# Input2.net
KiCad netlist of a schematic drawn in Altium Designer
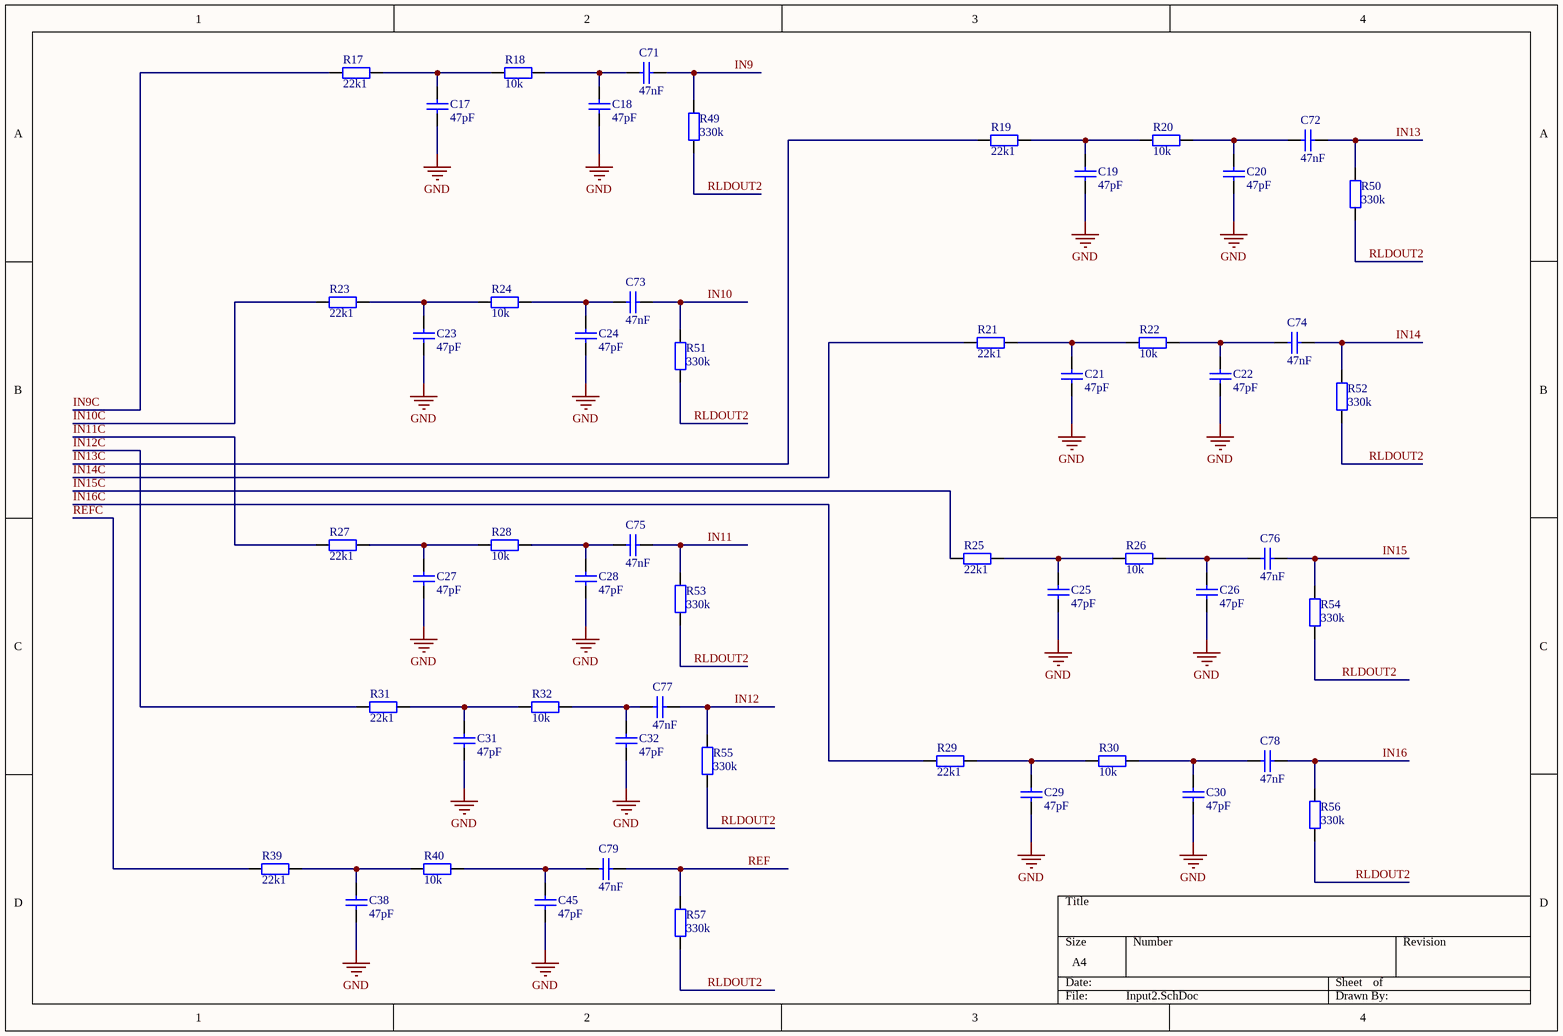
[diagram p0: Input2.SchDoc]

(export (version "E")
  (design (tool "Eeschema 10.0.6"))
  (components
    (comp (ref "C17")
      (value "47pF")
      (footprint "C0603")
      (description "Capacitor")
      (fields (field (name "PUBLISHER") "Altium Limited"))
      (libsource (lib "Miscellaneous Devices") (part "Cap"))
    )
    (comp (ref "C18")
      (value "47pF")
      (footprint "C0603")
      (description "Capacitor")
      (fields (field (name "PUBLISHER") "Altium Limited"))
      (libsource (lib "Miscellaneous Devices") (part "Cap"))
    )
    (comp (ref "C19")
      (value "47pF")
      (footprint "C0603")
      (description "Capacitor")
      (fields (field (name "PUBLISHER") "Altium Limited"))
      (libsource (lib "Miscellaneous Devices") (part "Cap"))
    )
    (comp (ref "C20")
      (value "47pF")
      (footprint "C0603")
      (description "Capacitor")
      (fields (field (name "PUBLISHER") "Altium Limited"))
      (libsource (lib "Miscellaneous Devices") (part "Cap"))
    )
    (comp (ref "C21")
      (value "47pF")
      (footprint "C0603")
      (description "Capacitor")
      (fields (field (name "PUBLISHER") "Altium Limited"))
      (libsource (lib "Miscellaneous Devices") (part "Cap"))
    )
    (comp (ref "C22")
      (value "47pF")
      (footprint "C0603")
      (description "Capacitor")
      (fields (field (name "PUBLISHER") "Altium Limited"))
      (libsource (lib "Miscellaneous Devices") (part "Cap"))
    )
    (comp (ref "C23")
      (value "47pF")
      (footprint "C0603")
      (description "Capacitor")
      (fields (field (name "PUBLISHER") "Altium Limited"))
      (libsource (lib "Miscellaneous Devices") (part "Cap"))
    )
    (comp (ref "C24")
      (value "47pF")
      (footprint "C0603")
      (description "Capacitor")
      (fields (field (name "PUBLISHER") "Altium Limited"))
      (libsource (lib "Miscellaneous Devices") (part "Cap"))
    )
    (comp (ref "C25")
      (value "47pF")
      (footprint "C0603")
      (description "Capacitor")
      (fields (field (name "PUBLISHER") "Altium Limited"))
      (libsource (lib "Miscellaneous Devices") (part "Cap"))
    )
    (comp (ref "C26")
      (value "47pF")
      (footprint "C0603")
      (description "Capacitor")
      (fields (field (name "PUBLISHER") "Altium Limited"))
      (libsource (lib "Miscellaneous Devices") (part "Cap"))
    )
    (comp (ref "C27")
      (value "47pF")
      (footprint "C0603")
      (description "Capacitor")
      (fields (field (name "PUBLISHER") "Altium Limited"))
      (libsource (lib "Miscellaneous Devices") (part "Cap"))
    )
    (comp (ref "C28")
      (value "47pF")
      (footprint "C0603")
      (description "Capacitor")
      (fields (field (name "PUBLISHER") "Altium Limited"))
      (libsource (lib "Miscellaneous Devices") (part "Cap"))
    )
    (comp (ref "C29")
      (value "47pF")
      (footprint "C0603")
      (description "Capacitor")
      (fields (field (name "PUBLISHER") "Altium Limited"))
      (libsource (lib "Miscellaneous Devices") (part "Cap"))
    )
    (comp (ref "C30")
      (value "47pF")
      (footprint "C0603")
      (description "Capacitor")
      (fields (field (name "PUBLISHER") "Altium Limited"))
      (libsource (lib "Miscellaneous Devices") (part "Cap"))
    )
    (comp (ref "C31")
      (value "47pF")
      (footprint "C0603")
      (description "Capacitor")
      (fields (field (name "PUBLISHER") "Altium Limited"))
      (libsource (lib "Miscellaneous Devices") (part "Cap"))
    )
    (comp (ref "C32")
      (value "47pF")
      (footprint "C0603")
      (description "Capacitor")
      (fields (field (name "PUBLISHER") "Altium Limited"))
      (libsource (lib "Miscellaneous Devices") (part "Cap"))
    )
    (comp (ref "C38")
      (value "47pF")
      (footprint "C0603")
      (description "Capacitor")
      (fields (field (name "PUBLISHER") "Altium Limited"))
      (libsource (lib "Miscellaneous Devices") (part "Cap"))
    )
    (comp (ref "C45")
      (value "47pF")
      (footprint "C0603")
      (description "Capacitor")
      (fields (field (name "PUBLISHER") "Altium Limited"))
      (libsource (lib "Miscellaneous Devices") (part "Cap"))
    )
    (comp (ref "C71")
      (value "47nF")
      (footprint "C0603")
      (description "Capacitor")
      (fields (field (name "PUBLISHER") "Altium Limited"))
      (libsource (lib "Miscellaneous Devices") (part "Cap"))
    )
    (comp (ref "C72")
      (value "47nF")
      (footprint "C0603")
      (description "Capacitor")
      (fields (field (name "PUBLISHER") "Altium Limited"))
      (libsource (lib "Miscellaneous Devices") (part "Cap"))
    )
    (comp (ref "C73")
      (value "47nF")
      (footprint "C0603")
      (description "Capacitor")
      (fields (field (name "PUBLISHER") "Altium Limited"))
      (libsource (lib "Miscellaneous Devices") (part "Cap"))
    )
    (comp (ref "C74")
      (value "47nF")
      (footprint "C0603")
      (description "Capacitor")
      (fields (field (name "PUBLISHER") "Altium Limited"))
      (libsource (lib "Miscellaneous Devices") (part "Cap"))
    )
    (comp (ref "C75")
      (value "47nF")
      (footprint "C0603")
      (description "Capacitor")
      (fields (field (name "PUBLISHER") "Altium Limited"))
      (libsource (lib "Miscellaneous Devices") (part "Cap"))
    )
    (comp (ref "C76")
      (value "47nF")
      (footprint "C0603")
      (description "Capacitor")
      (fields (field (name "PUBLISHER") "Altium Limited"))
      (libsource (lib "Miscellaneous Devices") (part "Cap"))
    )
    (comp (ref "C77")
      (value "47nF")
      (footprint "C0603")
      (description "Capacitor")
      (fields (field (name "PUBLISHER") "Altium Limited"))
      (libsource (lib "Miscellaneous Devices") (part "Cap"))
    )
    (comp (ref "C78")
      (value "47nF")
      (footprint "C0603")
      (description "Capacitor")
      (fields (field (name "PUBLISHER") "Altium Limited"))
      (libsource (lib "Miscellaneous Devices") (part "Cap"))
    )
    (comp (ref "C79")
      (value "47nF")
      (footprint "C0603")
      (description "Capacitor")
      (fields (field (name "PUBLISHER") "Altium Limited"))
      (libsource (lib "Miscellaneous Devices") (part "Cap"))
    )
    (comp (ref "R17")
      (value "22k1")
      (footprint "RES0603")
      (description "Resistor")
      (fields (field (name "PUBLISHER") "Altium Limited"))
      (libsource (lib "Miscellaneous Devices") (part "Res2"))
    )
    (comp (ref "R18")
      (value "10k")
      (footprint "RES0603")
      (description "Resistor")
      (fields (field (name "PUBLISHER") "Altium Limited"))
      (libsource (lib "Miscellaneous Devices") (part "Res2"))
    )
    (comp (ref "R19")
      (value "22k1")
      (footprint "RES0603")
      (description "Resistor")
      (fields (field (name "PUBLISHER") "Altium Limited"))
      (libsource (lib "Miscellaneous Devices") (part "Res2"))
    )
    (comp (ref "R20")
      (value "10k")
      (footprint "RES0603")
      (description "Resistor")
      (fields (field (name "PUBLISHER") "Altium Limited"))
      (libsource (lib "Miscellaneous Devices") (part "Res2"))
    )
    (comp (ref "R21")
      (value "22k1")
      (footprint "RES0603")
      (description "Resistor")
      (fields (field (name "PUBLISHER") "Altium Limited"))
      (libsource (lib "Miscellaneous Devices") (part "Res2"))
    )
    (comp (ref "R22")
      (value "10k")
      (footprint "RES0603")
      (description "Resistor")
      (fields (field (name "PUBLISHER") "Altium Limited"))
      (libsource (lib "Miscellaneous Devices") (part "Res2"))
    )
    (comp (ref "R23")
      (value "22k1")
      (footprint "RES0603")
      (description "Resistor")
      (fields (field (name "PUBLISHER") "Altium Limited"))
      (libsource (lib "Miscellaneous Devices") (part "Res2"))
    )
    (comp (ref "R24")
      (value "10k")
      (footprint "RES0603")
      (description "Resistor")
      (fields (field (name "PUBLISHER") "Altium Limited"))
      (libsource (lib "Miscellaneous Devices") (part "Res2"))
    )
    (comp (ref "R25")
      (value "22k1")
      (footprint "RES0603")
      (description "Resistor")
      (fields (field (name "PUBLISHER") "Altium Limited"))
      (libsource (lib "Miscellaneous Devices") (part "Res2"))
    )
    (comp (ref "R26")
      (value "10k")
      (footprint "RES0603")
      (description "Resistor")
      (fields (field (name "PUBLISHER") "Altium Limited"))
      (libsource (lib "Miscellaneous Devices") (part "Res2"))
    )
    (comp (ref "R27")
      (value "22k1")
      (footprint "RES0603")
      (description "Resistor")
      (fields (field (name "PUBLISHER") "Altium Limited"))
      (libsource (lib "Miscellaneous Devices") (part "Res2"))
    )
    (comp (ref "R28")
      (value "10k")
      (footprint "RES0603")
      (description "Resistor")
      (fields (field (name "PUBLISHER") "Altium Limited"))
      (libsource (lib "Miscellaneous Devices") (part "Res2"))
    )
    (comp (ref "R29")
      (value "22k1")
      (footprint "RES0603")
      (description "Resistor")
      (fields (field (name "PUBLISHER") "Altium Limited"))
      (libsource (lib "Miscellaneous Devices") (part "Res2"))
    )
    (comp (ref "R30")
      (value "10k")
      (footprint "RES0603")
      (description "Resistor")
      (fields (field (name "PUBLISHER") "Altium Limited"))
      (libsource (lib "Miscellaneous Devices") (part "Res2"))
    )
    (comp (ref "R31")
      (value "22k1")
      (footprint "RES0603")
      (description "Resistor")
      (fields (field (name "PUBLISHER") "Altium Limited"))
      (libsource (lib "Miscellaneous Devices") (part "Res2"))
    )
    (comp (ref "R32")
      (value "10k")
      (footprint "RES0603")
      (description "Resistor")
      (fields (field (name "PUBLISHER") "Altium Limited"))
      (libsource (lib "Miscellaneous Devices") (part "Res2"))
    )
    (comp (ref "R39")
      (value "22k1")
      (footprint "RES0603")
      (description "Resistor")
      (fields (field (name "PUBLISHER") "Altium Limited"))
      (libsource (lib "Miscellaneous Devices") (part "Res2"))
    )
    (comp (ref "R40")
      (value "10k")
      (footprint "RES0603")
      (description "Resistor")
      (fields (field (name "PUBLISHER") "Altium Limited"))
      (libsource (lib "Miscellaneous Devices") (part "Res2"))
    )
    (comp (ref "R49")
      (value "330k")
      (footprint "RES0603")
      (description "Resistor")
      (fields (field (name "PUBLISHER") "Altium Limited"))
      (libsource (lib "") (part "Res2_1"))
    )
    (comp (ref "R50")
      (value "330k")
      (footprint "RES0603")
      (description "Resistor")
      (fields (field (name "PUBLISHER") "Altium Limited"))
      (libsource (lib "") (part "Res2_1"))
    )
    (comp (ref "R51")
      (value "330k")
      (footprint "RES0603")
      (description "Resistor")
      (fields (field (name "PUBLISHER") "Altium Limited"))
      (libsource (lib "") (part "Res2_1"))
    )
    (comp (ref "R52")
      (value "330k")
      (footprint "RES0603")
      (description "Resistor")
      (fields (field (name "PUBLISHER") "Altium Limited"))
      (libsource (lib "") (part "Res2_1"))
    )
    (comp (ref "R53")
      (value "330k")
      (footprint "RES0603")
      (description "Resistor")
      (fields (field (name "PUBLISHER") "Altium Limited"))
      (libsource (lib "") (part "Res2_1"))
    )
    (comp (ref "R54")
      (value "330k")
      (footprint "RES0603")
      (description "Resistor")
      (fields (field (name "PUBLISHER") "Altium Limited"))
      (libsource (lib "") (part "Res2_1"))
    )
    (comp (ref "R55")
      (value "330k")
      (footprint "RES0603")
      (description "Resistor")
      (fields (field (name "PUBLISHER") "Altium Limited"))
      (libsource (lib "") (part "Res2_1"))
    )
    (comp (ref "R56")
      (value "330k")
      (footprint "RES0603")
      (description "Resistor")
      (fields (field (name "PUBLISHER") "Altium Limited"))
      (libsource (lib "") (part "Res2_1"))
    )
    (comp (ref "R57")
      (value "330k")
      (footprint "RES0603")
      (description "Resistor")
      (fields (field (name "PUBLISHER") "Altium Limited"))
      (libsource (lib "") (part "Res2_1"))
    )
  )
  (nets
    (net (code "1") (name "/IN9") (class "Default")
      (node (ref "C71") (pin "1") (pinfunction "1_1") (pintype "passive"))
      (node (ref "R49") (pin "2") (pinfunction "2_2") (pintype "passive"))
    )
    (net (code "2") (name "/IN9C") (class "Default")
      (node (ref "R17") (pin "1") (pinfunction "1_1") (pintype "passive"))
    )
    (net (code "3") (name "/IN10") (class "Default")
      (node (ref "C73") (pin "1") (pinfunction "1_1") (pintype "passive"))
      (node (ref "R51") (pin "2") (pinfunction "2_2") (pintype "passive"))
    )
    (net (code "4") (name "/IN10C") (class "Default")
      (node (ref "R23") (pin "1") (pinfunction "1_1") (pintype "passive"))
    )
    (net (code "5") (name "/IN11") (class "Default")
      (node (ref "C75") (pin "1") (pinfunction "1_1") (pintype "passive"))
      (node (ref "R53") (pin "2") (pinfunction "2_2") (pintype "passive"))
    )
    (net (code "6") (name "/IN11C") (class "Default")
      (node (ref "R27") (pin "1") (pinfunction "1_1") (pintype "passive"))
    )
    (net (code "7") (name "/IN12") (class "Default")
      (node (ref "C77") (pin "1") (pinfunction "1_1") (pintype "passive"))
      (node (ref "R55") (pin "2") (pinfunction "2_2") (pintype "passive"))
    )
    (net (code "8") (name "/IN12C") (class "Default")
      (node (ref "R31") (pin "1") (pinfunction "1_1") (pintype "passive"))
    )
    (net (code "9") (name "/IN13") (class "Default")
      (node (ref "C72") (pin "1") (pinfunction "1_1") (pintype "passive"))
      (node (ref "R50") (pin "2") (pinfunction "2_2") (pintype "passive"))
    )
    (net (code "10") (name "/IN13C") (class "Default")
      (node (ref "R19") (pin "1") (pinfunction "1_1") (pintype "passive"))
    )
    (net (code "11") (name "/IN14") (class "Default")
      (node (ref "C74") (pin "1") (pinfunction "1_1") (pintype "passive"))
      (node (ref "R52") (pin "2") (pinfunction "2_2") (pintype "passive"))
    )
    (net (code "12") (name "/IN14C") (class "Default")
      (node (ref "R21") (pin "1") (pinfunction "1_1") (pintype "passive"))
    )
    (net (code "13") (name "/IN15") (class "Default")
      (node (ref "C76") (pin "1") (pinfunction "1_1") (pintype "passive"))
      (node (ref "R54") (pin "2") (pinfunction "2_2") (pintype "passive"))
    )
    (net (code "14") (name "/IN15C") (class "Default")
      (node (ref "R25") (pin "1") (pinfunction "1_1") (pintype "passive"))
    )
    (net (code "15") (name "/IN16") (class "Default")
      (node (ref "C78") (pin "1") (pinfunction "1_1") (pintype "passive"))
      (node (ref "R56") (pin "2") (pinfunction "2_2") (pintype "passive"))
    )
    (net (code "16") (name "/IN16C") (class "Default")
      (node (ref "R29") (pin "1") (pinfunction "1_1") (pintype "passive"))
    )
    (net (code "17") (name "/REF") (class "Default")
      (node (ref "C79") (pin "1") (pinfunction "1_1") (pintype "passive"))
      (node (ref "R57") (pin "2") (pinfunction "2_2") (pintype "passive"))
    )
    (net (code "18") (name "/REFC") (class "Default")
      (node (ref "R39") (pin "1") (pinfunction "1_1") (pintype "passive"))
    )
    (net (code "19") (name "/RLDOUT2") (class "Default")
      (node (ref "R49") (pin "1") (pinfunction "1_1") (pintype "passive"))
      (node (ref "R50") (pin "1") (pinfunction "1_1") (pintype "passive"))
      (node (ref "R51") (pin "1") (pinfunction "1_1") (pintype "passive"))
      (node (ref "R52") (pin "1") (pinfunction "1_1") (pintype "passive"))
      (node (ref "R53") (pin "1") (pinfunction "1_1") (pintype "passive"))
      (node (ref "R54") (pin "1") (pinfunction "1_1") (pintype "passive"))
      (node (ref "R55") (pin "1") (pinfunction "1_1") (pintype "passive"))
      (node (ref "R56") (pin "1") (pinfunction "1_1") (pintype "passive"))
      (node (ref "R57") (pin "1") (pinfunction "1_1") (pintype "passive"))
    )
    (net (code "20") (name "GND") (class "Default")
      (node (ref "C17") (pin "1") (pinfunction "1_1") (pintype "passive"))
      (node (ref "C18") (pin "1") (pinfunction "1_1") (pintype "passive"))
      (node (ref "C19") (pin "1") (pinfunction "1_1") (pintype "passive"))
      (node (ref "C20") (pin "1") (pinfunction "1_1") (pintype "passive"))
      (node (ref "C21") (pin "1") (pinfunction "1_1") (pintype "passive"))
      (node (ref "C22") (pin "1") (pinfunction "1_1") (pintype "passive"))
      (node (ref "C23") (pin "1") (pinfunction "1_1") (pintype "passive"))
      (node (ref "C24") (pin "1") (pinfunction "1_1") (pintype "passive"))
      (node (ref "C25") (pin "1") (pinfunction "1_1") (pintype "passive"))
      (node (ref "C26") (pin "1") (pinfunction "1_1") (pintype "passive"))
      (node (ref "C27") (pin "1") (pinfunction "1_1") (pintype "passive"))
      (node (ref "C28") (pin "1") (pinfunction "1_1") (pintype "passive"))
      (node (ref "C29") (pin "1") (pinfunction "1_1") (pintype "passive"))
      (node (ref "C30") (pin "1") (pinfunction "1_1") (pintype "passive"))
      (node (ref "C31") (pin "1") (pinfunction "1_1") (pintype "passive"))
      (node (ref "C32") (pin "1") (pinfunction "1_1") (pintype "passive"))
      (node (ref "C38") (pin "1") (pinfunction "1_1") (pintype "passive"))
      (node (ref "C45") (pin "1") (pinfunction "1_1") (pintype "passive"))
    )
    (net (code "21") (name "Net-(C17-Pad2)") (class "Default")
      (node (ref "C17") (pin "2") (pinfunction "2_2") (pintype "passive"))
      (node (ref "R17") (pin "2") (pinfunction "2_2") (pintype "passive"))
      (node (ref "R18") (pin "1") (pinfunction "1_1") (pintype "passive"))
    )
    (net (code "22") (name "Net-(C18-Pad2)") (class "Default")
      (node (ref "C18") (pin "2") (pinfunction "2_2") (pintype "passive"))
      (node (ref "C71") (pin "2") (pinfunction "2_2") (pintype "passive"))
      (node (ref "R18") (pin "2") (pinfunction "2_2") (pintype "passive"))
    )
    (net (code "23") (name "Net-(C19-Pad2)") (class "Default")
      (node (ref "C19") (pin "2") (pinfunction "2_2") (pintype "passive"))
      (node (ref "R19") (pin "2") (pinfunction "2_2") (pintype "passive"))
      (node (ref "R20") (pin "1") (pinfunction "1_1") (pintype "passive"))
    )
    (net (code "24") (name "Net-(C20-Pad2)") (class "Default")
      (node (ref "C20") (pin "2") (pinfunction "2_2") (pintype "passive"))
      (node (ref "C72") (pin "2") (pinfunction "2_2") (pintype "passive"))
      (node (ref "R20") (pin "2") (pinfunction "2_2") (pintype "passive"))
    )
    (net (code "25") (name "Net-(C21-Pad2)") (class "Default")
      (node (ref "C21") (pin "2") (pinfunction "2_2") (pintype "passive"))
      (node (ref "R21") (pin "2") (pinfunction "2_2") (pintype "passive"))
      (node (ref "R22") (pin "1") (pinfunction "1_1") (pintype "passive"))
    )
    (net (code "26") (name "Net-(C22-Pad2)") (class "Default")
      (node (ref "C22") (pin "2") (pinfunction "2_2") (pintype "passive"))
      (node (ref "C74") (pin "2") (pinfunction "2_2") (pintype "passive"))
      (node (ref "R22") (pin "2") (pinfunction "2_2") (pintype "passive"))
    )
    (net (code "27") (name "Net-(C23-Pad2)") (class "Default")
      (node (ref "C23") (pin "2") (pinfunction "2_2") (pintype "passive"))
      (node (ref "R23") (pin "2") (pinfunction "2_2") (pintype "passive"))
      (node (ref "R24") (pin "1") (pinfunction "1_1") (pintype "passive"))
    )
    (net (code "28") (name "Net-(C24-Pad2)") (class "Default")
      (node (ref "C24") (pin "2") (pinfunction "2_2") (pintype "passive"))
      (node (ref "C73") (pin "2") (pinfunction "2_2") (pintype "passive"))
      (node (ref "R24") (pin "2") (pinfunction "2_2") (pintype "passive"))
    )
    (net (code "29") (name "Net-(C25-Pad2)") (class "Default")
      (node (ref "C25") (pin "2") (pinfunction "2_2") (pintype "passive"))
      (node (ref "R25") (pin "2") (pinfunction "2_2") (pintype "passive"))
      (node (ref "R26") (pin "1") (pinfunction "1_1") (pintype "passive"))
    )
    (net (code "30") (name "Net-(C26-Pad2)") (class "Default")
      (node (ref "C26") (pin "2") (pinfunction "2_2") (pintype "passive"))
      (node (ref "C76") (pin "2") (pinfunction "2_2") (pintype "passive"))
      (node (ref "R26") (pin "2") (pinfunction "2_2") (pintype "passive"))
    )
    (net (code "31") (name "Net-(C27-Pad2)") (class "Default")
      (node (ref "C27") (pin "2") (pinfunction "2_2") (pintype "passive"))
      (node (ref "R27") (pin "2") (pinfunction "2_2") (pintype "passive"))
      (node (ref "R28") (pin "1") (pinfunction "1_1") (pintype "passive"))
    )
    (net (code "32") (name "Net-(C28-Pad2)") (class "Default")
      (node (ref "C28") (pin "2") (pinfunction "2_2") (pintype "passive"))
      (node (ref "C75") (pin "2") (pinfunction "2_2") (pintype "passive"))
      (node (ref "R28") (pin "2") (pinfunction "2_2") (pintype "passive"))
    )
    (net (code "33") (name "Net-(C29-Pad2)") (class "Default")
      (node (ref "C29") (pin "2") (pinfunction "2_2") (pintype "passive"))
      (node (ref "R29") (pin "2") (pinfunction "2_2") (pintype "passive"))
      (node (ref "R30") (pin "1") (pinfunction "1_1") (pintype "passive"))
    )
    (net (code "34") (name "Net-(C30-Pad2)") (class "Default")
      (node (ref "C30") (pin "2") (pinfunction "2_2") (pintype "passive"))
      (node (ref "C78") (pin "2") (pinfunction "2_2") (pintype "passive"))
      (node (ref "R30") (pin "2") (pinfunction "2_2") (pintype "passive"))
    )
    (net (code "35") (name "Net-(C31-Pad2)") (class "Default")
      (node (ref "C31") (pin "2") (pinfunction "2_2") (pintype "passive"))
      (node (ref "R31") (pin "2") (pinfunction "2_2") (pintype "passive"))
      (node (ref "R32") (pin "1") (pinfunction "1_1") (pintype "passive"))
    )
    (net (code "36") (name "Net-(C32-Pad2)") (class "Default")
      (node (ref "C32") (pin "2") (pinfunction "2_2") (pintype "passive"))
      (node (ref "C77") (pin "2") (pinfunction "2_2") (pintype "passive"))
      (node (ref "R32") (pin "2") (pinfunction "2_2") (pintype "passive"))
    )
    (net (code "37") (name "Net-(C38-Pad2)") (class "Default")
      (node (ref "C38") (pin "2") (pinfunction "2_2") (pintype "passive"))
      (node (ref "R39") (pin "2") (pinfunction "2_2") (pintype "passive"))
      (node (ref "R40") (pin "1") (pinfunction "1_1") (pintype "passive"))
    )
    (net (code "38") (name "Net-(C45-Pad2)") (class "Default")
      (node (ref "C45") (pin "2") (pinfunction "2_2") (pintype "passive"))
      (node (ref "C79") (pin "2") (pinfunction "2_2") (pintype "passive"))
      (node (ref "R40") (pin "2") (pinfunction "2_2") (pintype "passive"))
    )
  )
)
